# Schematic_SensorTapeFlex_v1.net
KiCad netlist of a schematic drawn in Altium Designer
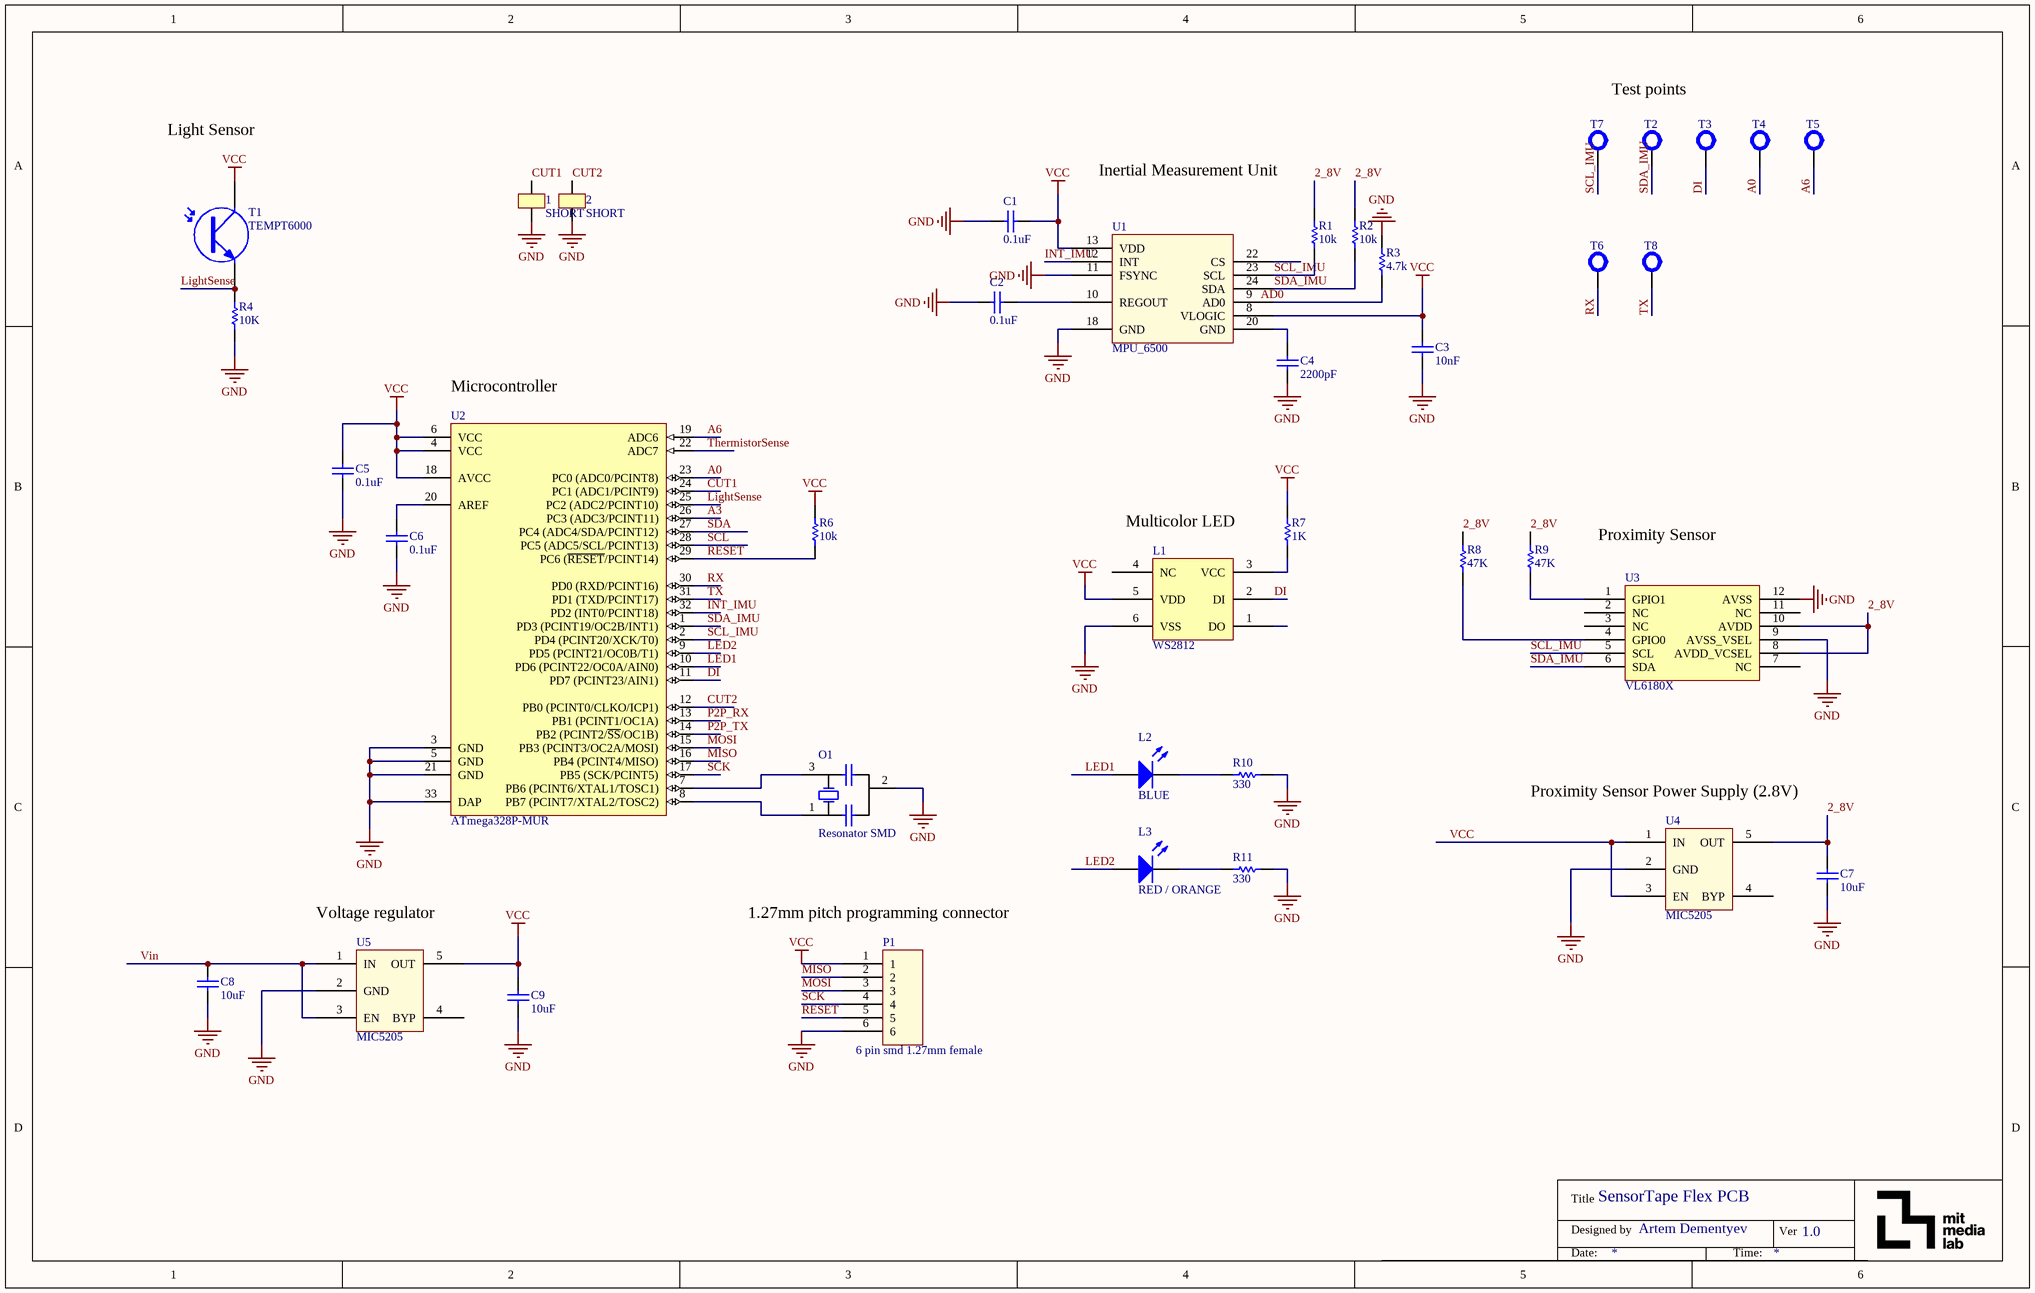
[diagram p0: Schematic_SensorTapeFlex_v1.SchDoc]

(export (version "E")
  (design (tool "Eeschema 10.0.6"))
  (components
    (comp (ref "1") (value "SHORT") (footprint "SHORT") (libsource (lib "Artem_Library") (part "SHORT")))
    (comp (ref "2") (value "SHORT") (footprint "SHORT") (libsource (lib "Artem_Library") (part "SHORT")))
    (comp (ref "C1")
      (value "0.1uF")
      (footprint "0603W")
      (description "SMD Cap 1206")
      (libsource (lib "Artem_Library") (part "Capacitor"))
    )
    (comp (ref "C2")
      (value "0.1uF")
      (footprint "0603W")
      (description "SMD Cap 1206")
      (libsource (lib "Artem_Library") (part "Capacitor"))
    )
    (comp (ref "C3")
      (value "10nF")
      (footprint "0603W")
      (description "SMD Cap 1206")
      (libsource (lib "Artem_Library") (part "Capacitor"))
    )
    (comp (ref "C4")
      (value "2200pF")
      (footprint "0603W")
      (description "SMD Cap 1206")
      (libsource (lib "Artem_Library") (part "Capacitor"))
    )
    (comp (ref "C5")
      (value "0.1uF")
      (footprint "0603W")
      (description "SMD Cap 1206")
      (libsource (lib "Artem_Library") (part "Capacitor"))
    )
    (comp (ref "C6")
      (value "0.1uF")
      (footprint "0603W")
      (description "SMD Cap 1206")
      (libsource (lib "Artem_Library") (part "Capacitor"))
    )
    (comp (ref "C7")
      (value "10uF")
      (footprint "0603W")
      (description "SMD Cap 1206")
      (libsource (lib "Artem_Library") (part "Capacitor"))
    )
    (comp (ref "C8")
      (value "10uF")
      (footprint "0603W")
      (description "SMD Cap 1206")
      (libsource (lib "Artem_Library") (part "Capacitor"))
    )
    (comp (ref "C9")
      (value "10uF")
      (footprint "0603W")
      (description "SMD Cap 1206")
      (libsource (lib "Artem_Library") (part "Capacitor"))
    )
    (comp (ref "L1") (value "WS2812") (footprint "WS2812") (libsource (lib "Artem_Library") (part "WS2812")))
    (comp (ref "L2")
      (value "BLUE")
      (footprint "0603W")
      (description "LED SMD 1206/0603")
      (libsource (lib "Artem_Library") (part "LED"))
    )
    (comp (ref "L3")
      (value "RED / ORANGE")
      (footprint "0603W")
      (description "LED SMD 1206/0603")
      (libsource (lib "Artem_Library") (part "LED"))
    )
    (comp (ref "O1")
      (value "Resonator SMD")
      (footprint "Resonator SMD")
      (description "Build in caps")
      (libsource (lib "Artem_Library") (part "Resonator SMD"))
    )
    (comp (ref "P1")
      (value "6 pin smd 1.27mm female")
      (footprint "6pos 1.27mm")
      (libsource (lib "Artem_Library") (part "6 pin smd 1.27mm female"))
    )
    (comp (ref "R1") (value "10k") (footprint "0603W") (libsource (lib "Artem_Library") (part "Resistor")))
    (comp (ref "R2") (value "10k") (footprint "0603W") (libsource (lib "Artem_Library") (part "Resistor")))
    (comp (ref "R3") (value "4.7k") (footprint "0603W") (libsource (lib "Artem_Library") (part "Resistor")))
    (comp (ref "R4") (value "10K") (footprint "0603W") (libsource (lib "Artem_Library") (part "Resistor")))
    (comp (ref "R6") (value "10k") (footprint "0603W") (libsource (lib "Artem_Library") (part "Resistor")))
    (comp (ref "R7") (value "1K") (footprint "0603W") (libsource (lib "Artem_Library") (part "Resistor")))
    (comp (ref "R8") (value "47K") (footprint "0603W") (libsource (lib "Artem_Library") (part "Resistor")))
    (comp (ref "R9") (value "47K") (footprint "0603W") (libsource (lib "Artem_Library") (part "Resistor")))
    (comp (ref "R10") (value "330") (footprint "0603W") (libsource (lib "Artem_Library") (part "Resistor")))
    (comp (ref "R11") (value "330") (footprint "0603W") (libsource (lib "Artem_Library") (part "Resistor")))
    (comp (ref "T1")
      (value "TEMPT6000")
      (footprint "TEMP6000")
      (libsource (lib "Artem_Library") (part "TEMPT6000"))
    )
    (comp (ref "T2")
      (value "~")
      (footprint "TEST POINT SMD SUPER SMALL")
      (libsource (lib "Artem_Library") (part "Test point small"))
    )
    (comp (ref "T3")
      (value "~")
      (footprint "TEST POINT SMD SUPER SMALL")
      (libsource (lib "Artem_Library") (part "Test point small"))
    )
    (comp (ref "T4")
      (value "~")
      (footprint "TEST POINT SMD SUPER SMALL")
      (libsource (lib "Artem_Library") (part "Test point small"))
    )
    (comp (ref "T5")
      (value "~")
      (footprint "TEST POINT SMD SUPER SMALL")
      (libsource (lib "Artem_Library") (part "Test point small"))
    )
    (comp (ref "T6")
      (value "~")
      (footprint "TEST POINT SMD SUPER SMALL")
      (libsource (lib "Artem_Library") (part "Test point small"))
    )
    (comp (ref "T7")
      (value "~")
      (footprint "TEST POINT SMD SUPER SMALL")
      (libsource (lib "Artem_Library") (part "Test point small"))
    )
    (comp (ref "T8")
      (value "~")
      (footprint "TEST POINT SMD SUPER SMALL")
      (libsource (lib "Artem_Library") (part "Test point small"))
    )
    (comp (ref "U1")
      (value "MPU_6500")
      (footprint "QFN24")
      (description "Gyro / accelerometer combo")
      (libsource (lib "Artem_Library") (part "MPU_6500"))
    )
    (comp (ref "U2")
      (value "ATmega328P-MUR")
      (footprint "32M1-A_M")
      (libsource (lib "Atmel Microcontroller 8-Bit megaAVR") (part "ATmega328P-MUR"))
    )
    (comp (ref "U3")
      (value "VL6180X")
      (footprint "VL6180X")
      (libsource (lib "Artem_Library") (part "VL6180X"))
    )
    (comp (ref "U4")
      (value "MIC5205")
      (footprint "SOT-23-5")
      (description "2.8V LDO SMD")
      (libsource (lib "Artem_Library") (part "MIC5205_VOLTAGE_REG"))
    )
    (comp (ref "U5")
      (value "MIC5205")
      (footprint "SOT-23-5")
      (description "3.3V LDO SMD")
      (libsource (lib "Artem_Library") (part "MIC5205_VOLTAGE_REG"))
    )
  )
  (nets
    (net (code "1") (name "/2_8V") (class "Default")
      (node (ref "C7") (pin "2") (pinfunction "2_2") (pintype "passive"))
      (node (ref "R1") (pin "2") (pinfunction "2_2") (pintype "passive"))
      (node (ref "R2") (pin "2") (pinfunction "2_2") (pintype "passive"))
      (node (ref "R8") (pin "2") (pinfunction "2_2") (pintype "passive"))
      (node (ref "R9") (pin "2") (pinfunction "2_2") (pintype "passive"))
      (node (ref "U3") (pin "10") (pinfunction "AVDD_10") (pintype "passive"))
      (node (ref "U3") (pin "8") (pinfunction "AVDD_VCSEL_8") (pintype "passive"))
      (node (ref "U4") (pin "5") (pinfunction "OUT_5") (pintype "passive"))
    )
    (net (code "2") (name "/A0") (class "Default")
      (node (ref "T4") (pin "0") (pinfunction "0_0") (pintype "passive"))
      (node (ref "U2") (pin "23") (pinfunction "PC0_(ADC0/PCINT8)_23") (pintype "bidirectional"))
    )
    (net (code "3") (name "/A3") (class "Default")
      (node (ref "U2") (pin "26") (pinfunction "PC3_(ADC3/PCINT11)_26") (pintype "bidirectional"))
    )
    (net (code "4") (name "/A6") (class "Default")
      (node (ref "T5") (pin "0") (pinfunction "0_0") (pintype "passive"))
      (node (ref "U2") (pin "19") (pinfunction "ADC6_19") (pintype "input"))
    )
    (net (code "6") (name "/CUT1") (class "Default")
      (node (ref "1") (pin "1") (pinfunction "1_1") (pintype "passive"))
      (node (ref "U2") (pin "24") (pinfunction "PC1_(ADC1/PCINT9)_24") (pintype "bidirectional"))
    )
    (net (code "7") (name "/CUT2") (class "Default")
      (node (ref "2") (pin "1") (pinfunction "1_1") (pintype "passive"))
      (node (ref "U2") (pin "12") (pinfunction "PB0_(PCINT0/CLKO/ICP1)_12") (pintype "bidirectional"))
    )
    (net (code "8") (name "/DI") (class "Default")
      (node (ref "L1") (pin "2") (pinfunction "DI_2") (pintype "passive"))
      (node (ref "T3") (pin "0") (pinfunction "0_0") (pintype "passive"))
      (node (ref "U2") (pin "11") (pinfunction "PD7_(PCINT23/AIN1)_11") (pintype "bidirectional"))
    )
    (net (code "9") (name "/INT_IMU") (class "Default")
      (node (ref "U1") (pin "12") (pinfunction "INT_12") (pintype "passive"))
      (node (ref "U2") (pin "32") (pinfunction "PD2_(INT0/PCINT18)_32") (pintype "bidirectional"))
    )
    (net (code "10") (name "/LED1") (class "Default")
      (node (ref "L2") (pin "1") (pinfunction "A_1") (pintype "passive"))
      (node (ref "U2") (pin "10") (pinfunction "PD6_(PCINT22/OC0A/AIN0)_10") (pintype "bidirectional"))
    )
    (net (code "11") (name "/LED2") (class "Default")
      (node (ref "L3") (pin "1") (pinfunction "A_1") (pintype "passive"))
      (node (ref "U2") (pin "9") (pinfunction "PD5_(PCINT21/OC0B/T1)_9") (pintype "bidirectional"))
    )
    (net (code "12") (name "/LightSense") (class "Default")
      (node (ref "R4") (pin "2") (pinfunction "2_2") (pintype "passive"))
      (node (ref "T1") (pin "2") (pinfunction "E_2") (pintype "passive"))
      (node (ref "U2") (pin "25") (pinfunction "PC2_(ADC2/PCINT10)_25") (pintype "bidirectional"))
    )
    (net (code "13") (name "/MISO") (class "Default")
      (node (ref "P1") (pin "2") (pinfunction "2_2") (pintype "passive"))
      (node (ref "U2") (pin "16") (pinfunction "PB4_(PCINT4/MISO)_16") (pintype "bidirectional"))
    )
    (net (code "14") (name "/MOSI") (class "Default")
      (node (ref "P1") (pin "3") (pinfunction "3_3") (pintype "passive"))
      (node (ref "U2") (pin "15") (pinfunction "PB3_(PCINT3/OC2A/MOSI)_15") (pintype "bidirectional"))
    )
    (net (code "15") (name "/P2P_RX") (class "Default")
      (node (ref "U2") (pin "13") (pinfunction "PB1_(PCINT1/OC1A)_13") (pintype "bidirectional"))
    )
    (net (code "16") (name "/P2P_TX") (class "Default")
      (node (ref "U2") (pin "14") (pinfunction "PB2_(PCINT2/~{SS}/OC1B)_14") (pintype "bidirectional"))
    )
    (net (code "17") (name "/RESET") (class "Default")
      (node (ref "P1") (pin "5") (pinfunction "5_5") (pintype "passive"))
      (node (ref "R6") (pin "1") (pinfunction "1_1") (pintype "passive"))
      (node (ref "U2") (pin "29") (pinfunction "PC6_(~{RESET}/PCINT14)_29") (pintype "bidirectional"))
    )
    (net (code "18") (name "/RX") (class "Default")
      (node (ref "T6") (pin "0") (pinfunction "0_0") (pintype "passive"))
      (node (ref "U2") (pin "30") (pinfunction "PD0_(RXD/PCINT16)_30") (pintype "bidirectional"))
    )
    (net (code "19") (name "/SCK") (class "Default")
      (node (ref "P1") (pin "4") (pinfunction "4_4") (pintype "passive"))
      (node (ref "U2") (pin "17") (pinfunction "PB5_(SCK/PCINT5)_17") (pintype "bidirectional"))
    )
    (net (code "20") (name "/SCL") (class "Default")
      (node (ref "U2") (pin "28") (pinfunction "PC5_(ADC5/SCL/PCINT13)_28") (pintype "bidirectional"))
    )
    (net (code "21") (name "/SCL_IMU") (class "Default")
      (node (ref "R1") (pin "1") (pinfunction "1_1") (pintype "passive"))
      (node (ref "T7") (pin "0") (pinfunction "0_0") (pintype "passive"))
      (node (ref "U1") (pin "23") (pinfunction "SCL_23") (pintype "passive"))
      (node (ref "U2") (pin "2") (pinfunction "PD4_(PCINT20/XCK/T0)_2") (pintype "bidirectional"))
      (node (ref "U3") (pin "5") (pinfunction "SCL_5") (pintype "passive"))
    )
    (net (code "22") (name "/SDA") (class "Default")
      (node (ref "U2") (pin "27") (pinfunction "PC4_(ADC4/SDA/PCINT12)_27") (pintype "bidirectional"))
    )
    (net (code "23") (name "/SDA_IMU") (class "Default")
      (node (ref "R2") (pin "1") (pinfunction "1_1") (pintype "passive"))
      (node (ref "T2") (pin "0") (pinfunction "0_0") (pintype "passive"))
      (node (ref "U1") (pin "24") (pinfunction "SDA_24") (pintype "passive"))
      (node (ref "U2") (pin "1") (pinfunction "PD3_(PCINT19/OC2B/INT1)_1") (pintype "bidirectional"))
      (node (ref "U3") (pin "6") (pinfunction "SDA_6") (pintype "passive"))
    )
    (net (code "24") (name "/TX") (class "Default")
      (node (ref "T8") (pin "0") (pinfunction "0_0") (pintype "passive"))
      (node (ref "U2") (pin "31") (pinfunction "PD1_(TXD/PCINT17)_31") (pintype "bidirectional"))
    )
    (net (code "25") (name "/ThermistorSense") (class "Default")
      (node (ref "U2") (pin "22") (pinfunction "ADC7_22") (pintype "input"))
    )
    (net (code "26") (name "/Vin") (class "Default")
      (node (ref "C8") (pin "2") (pinfunction "2_2") (pintype "passive"))
      (node (ref "U5") (pin "1") (pinfunction "IN_1") (pintype "passive"))
      (node (ref "U5") (pin "3") (pinfunction "EN_3") (pintype "passive"))
    )
    (net (code "27") (name "GND") (class "Default")
      (node (ref "1") (pin "0") (pinfunction "0_0") (pintype "passive"))
      (node (ref "2") (pin "0") (pinfunction "0_0") (pintype "passive"))
      (node (ref "C1") (pin "2") (pinfunction "2_2") (pintype "passive"))
      (node (ref "C2") (pin "2") (pinfunction "2_2") (pintype "passive"))
      (node (ref "C3") (pin "2") (pinfunction "2_2") (pintype "passive"))
      (node (ref "C4") (pin "2") (pinfunction "2_2") (pintype "passive"))
      (node (ref "C5") (pin "1") (pinfunction "1_1") (pintype "passive"))
      (node (ref "C6") (pin "1") (pinfunction "1_1") (pintype "passive"))
      (node (ref "C7") (pin "1") (pinfunction "1_1") (pintype "passive"))
      (node (ref "C8") (pin "1") (pinfunction "1_1") (pintype "passive"))
      (node (ref "C9") (pin "1") (pinfunction "1_1") (pintype "passive"))
      (node (ref "L1") (pin "6") (pinfunction "VSS_6") (pintype "passive"))
      (node (ref "O1") (pin "2") (pinfunction "2_2") (pintype "passive"))
      (node (ref "P1") (pin "6") (pinfunction "6_6") (pintype "passive"))
      (node (ref "R10") (pin "1") (pinfunction "1_1") (pintype "passive"))
      (node (ref "R11") (pin "1") (pinfunction "1_1") (pintype "passive"))
      (node (ref "R3") (pin "2") (pinfunction "2_2") (pintype "passive"))
      (node (ref "R4") (pin "1") (pinfunction "1_1") (pintype "passive"))
      (node (ref "U1") (pin "11") (pinfunction "FSYNC_11") (pintype "passive"))
      (node (ref "U1") (pin "18") (pinfunction "GND_18") (pintype "passive"))
      (node (ref "U2") (pin "21") (pinfunction "GND_21") (pintype "power_in"))
      (node (ref "U2") (pin "3") (pinfunction "GND_3") (pintype "power_in"))
      (node (ref "U2") (pin "33") (pinfunction "DAP_33") (pintype "power_in"))
      (node (ref "U2") (pin "5") (pinfunction "GND_5") (pintype "power_in"))
      (node (ref "U3") (pin "12") (pinfunction "AVSS_12") (pintype "passive"))
      (node (ref "U3") (pin "9") (pinfunction "AVSS_VSEL_9") (pintype "passive"))
      (node (ref "U4") (pin "2") (pinfunction "GND_2") (pintype "passive"))
      (node (ref "U5") (pin "2") (pinfunction "GND_2") (pintype "passive"))
    )
    (net (code "28") (name "Net-(C4-Pad1)") (class "Default")
      (node (ref "C4") (pin "1") (pinfunction "1_1") (pintype "passive"))
      (node (ref "U1") (pin "20") (pinfunction "GND_20") (pintype "passive"))
    )
    (net (code "29") (name "Net-(L1-VCC)") (class "Default")
      (node (ref "L1") (pin "3") (pinfunction "VCC_3") (pintype "passive"))
      (node (ref "R7") (pin "1") (pinfunction "1_1") (pintype "passive"))
    )
    (net (code "30") (name "Net-(L2-K)") (class "Default")
      (node (ref "L2") (pin "2") (pinfunction "K_2") (pintype "passive"))
      (node (ref "R10") (pin "2") (pinfunction "2_2") (pintype "passive"))
    )
    (net (code "31") (name "Net-(L3-K)") (class "Default")
      (node (ref "L3") (pin "2") (pinfunction "K_2") (pintype "passive"))
      (node (ref "R11") (pin "2") (pinfunction "2_2") (pintype "passive"))
    )
    (net (code "32") (name "Net-(U1-AD0)") (class "Default")
      (node (ref "R3") (pin "1") (pinfunction "1_1") (pintype "passive"))
      (node (ref "U1") (pin "9") (pinfunction "AD0_9") (pintype "passive"))
    )
    (net (code "33") (name "Net-(U1-REGOUT)") (class "Default")
      (node (ref "C2") (pin "1") (pinfunction "1_1") (pintype "passive"))
      (node (ref "U1") (pin "10") (pinfunction "REGOUT_10") (pintype "passive"))
    )
    (net (code "34") (name "Net-(U2-AREF)") (class "Default")
      (node (ref "C6") (pin "2") (pinfunction "2_2") (pintype "passive"))
      (node (ref "U2") (pin "20") (pinfunction "AREF_20") (pintype "passive"))
    )
    (net (code "35") (name "Net-(U2-PB6_(PCINT6{slash}XTAL1{slash}TOSC1))") (class "Default")
      (node (ref "O1") (pin "3") (pinfunction "3_3") (pintype "passive"))
      (node (ref "U2") (pin "7") (pinfunction "PB6_(PCINT6/XTAL1/TOSC1)_7") (pintype "bidirectional"))
    )
    (net (code "36") (name "Net-(U2-PB7_(PCINT7{slash}XTAL2{slash}TOSC2))") (class "Default")
      (node (ref "O1") (pin "1") (pinfunction "1_1") (pintype "passive"))
      (node (ref "U2") (pin "8") (pinfunction "PB7_(PCINT7/XTAL2/TOSC2)_8") (pintype "bidirectional"))
    )
    (net (code "37") (name "Net-(U3-GPIO0)") (class "Default")
      (node (ref "R8") (pin "1") (pinfunction "1_1") (pintype "passive"))
      (node (ref "U3") (pin "4") (pinfunction "GPIO0_4") (pintype "passive"))
    )
    (net (code "38") (name "Net-(U3-GPIO1)") (class "Default")
      (node (ref "R9") (pin "1") (pinfunction "1_1") (pintype "passive"))
      (node (ref "U3") (pin "1") (pinfunction "GPIO1_1") (pintype "passive"))
    )
    (net (code "39") (name "VCC") (class "Default")
      (node (ref "C1") (pin "1") (pinfunction "1_1") (pintype "passive"))
      (node (ref "C3") (pin "1") (pinfunction "1_1") (pintype "passive"))
      (node (ref "C5") (pin "2") (pinfunction "2_2") (pintype "passive"))
      (node (ref "C9") (pin "2") (pinfunction "2_2") (pintype "passive"))
      (node (ref "L1") (pin "5") (pinfunction "VDD_5") (pintype "passive"))
      (node (ref "P1") (pin "1") (pinfunction "1_1") (pintype "passive"))
      (node (ref "R6") (pin "2") (pinfunction "2_2") (pintype "passive"))
      (node (ref "R7") (pin "2") (pinfunction "2_2") (pintype "passive"))
      (node (ref "T1") (pin "1") (pinfunction "C_1") (pintype "passive"))
      (node (ref "U1") (pin "13") (pinfunction "VDD_13") (pintype "passive"))
      (node (ref "U1") (pin "8") (pinfunction "VLOGIC_8") (pintype "passive"))
      (node (ref "U2") (pin "18") (pinfunction "AVCC_18") (pintype "power_in"))
      (node (ref "U2") (pin "4") (pinfunction "VCC_4") (pintype "power_in"))
      (node (ref "U2") (pin "6") (pinfunction "VCC_6") (pintype "power_in"))
      (node (ref "U4") (pin "1") (pinfunction "IN_1") (pintype "passive"))
      (node (ref "U4") (pin "3") (pinfunction "EN_3") (pintype "passive"))
      (node (ref "U5") (pin "5") (pinfunction "OUT_5") (pintype "passive"))
    )
    (net (code "40") (name "unconnected-(L1-DO-Pad1)") (class "Default")
      (node (ref "L1") (pin "1") (pinfunction "DO_1") (pintype "passive"))
    )
    (net (code "41") (name "unconnected-(L1-NC-Pad4)") (class "Default")
      (node (ref "L1") (pin "4") (pinfunction "NC_4") (pintype "passive"))
    )
    (net (code "42") (name "unconnected-(U1-CS-Pad22)") (class "Default")
      (node (ref "U1") (pin "22") (pinfunction "CS_22") (pintype "passive"))
    )
    (net (code "43") (name "unconnected-(U3-NC-Pad2)") (class "Default")
      (node (ref "U3") (pin "2") (pinfunction "NC_2") (pintype "passive"))
    )
    (net (code "44") (name "unconnected-(U3-NC-Pad3)") (class "Default")
      (node (ref "U3") (pin "3") (pinfunction "NC_3") (pintype "passive"))
    )
    (net (code "45") (name "unconnected-(U3-NC-Pad7)") (class "Default")
      (node (ref "U3") (pin "7") (pinfunction "NC_7") (pintype "passive"))
    )
    (net (code "46") (name "unconnected-(U3-NC-Pad11)") (class "Default")
      (node (ref "U3") (pin "11") (pinfunction "NC_11") (pintype "passive"))
    )
    (net (code "47") (name "unconnected-(U4-BYP-Pad4)") (class "Default")
      (node (ref "U4") (pin "4") (pinfunction "BYP_4") (pintype "passive"))
    )
    (net (code "48") (name "unconnected-(U5-BYP-Pad4)") (class "Default")
      (node (ref "U5") (pin "4") (pinfunction "BYP_4") (pintype "passive"))
    )
  )
)
